# STM32.net
KiCad netlist of a schematic drawn in Altium Designer
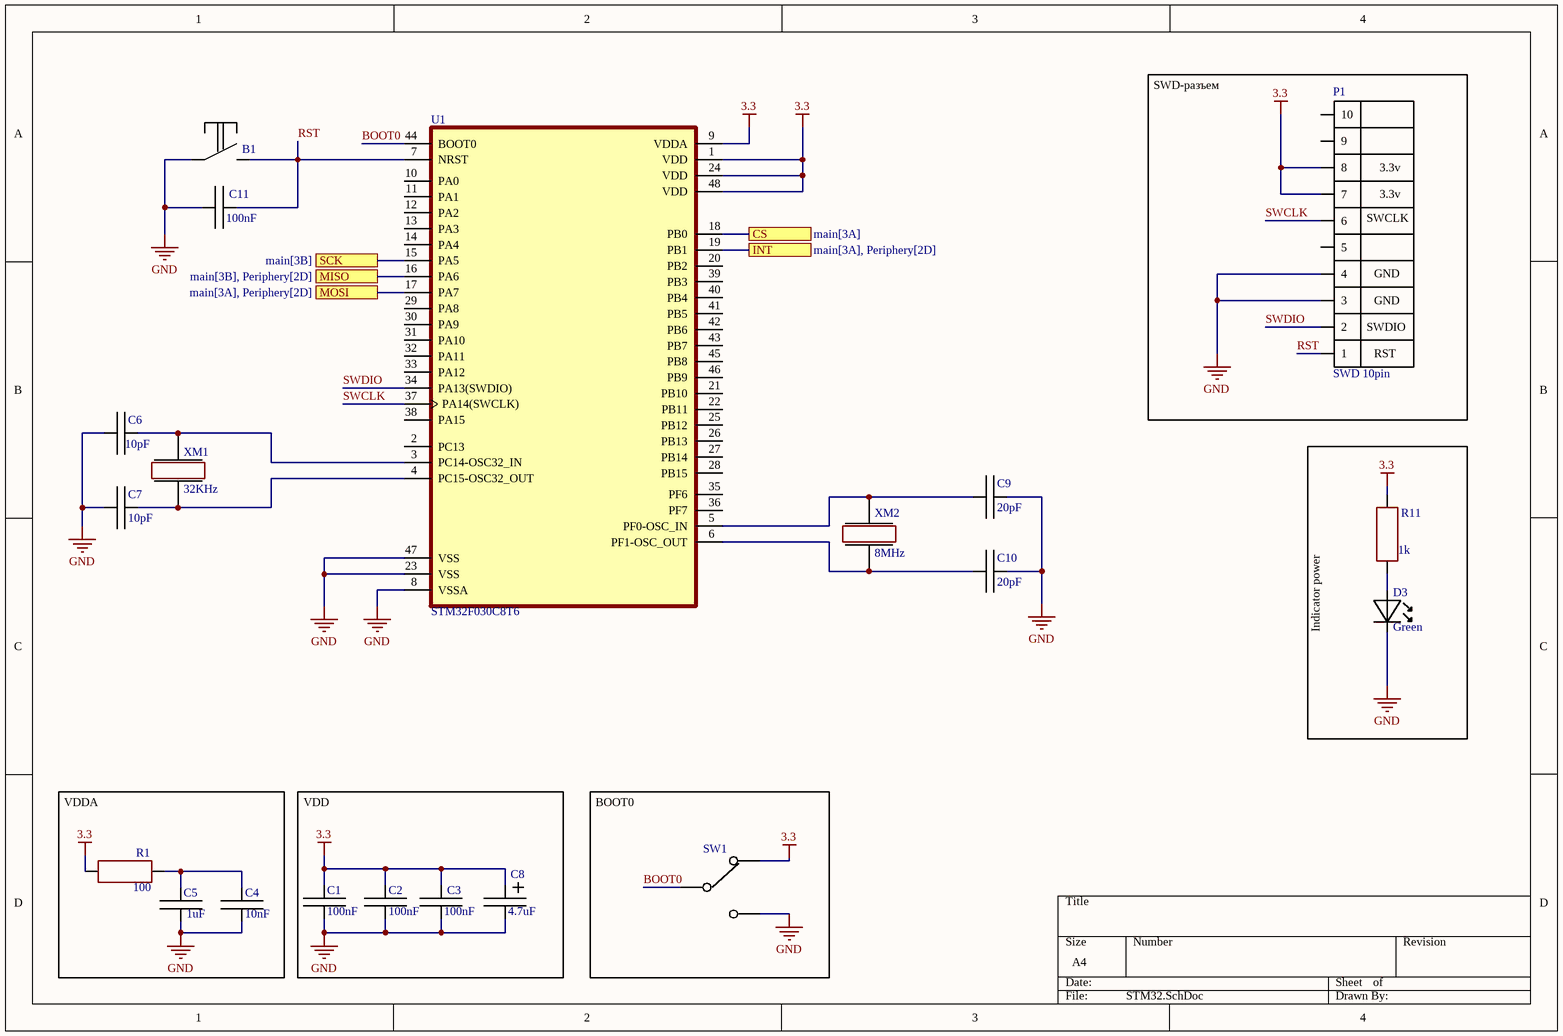
[diagram p0: STM32.SchDoc]

(export (version "E")
  (design (tool "Eeschema 10.0.6"))
  (components
    (comp (ref "B1")
      (value "Knopka")
      (footprint "knopka")
      (description "SMD")
      (libsource (lib "Integrated_Library1") (part "Knopka"))
    )
    (comp (ref "C1")
      (value "100nF")
      (footprint "C0805")
      (description "Керамический конденсатор. 1uF,10uF,106uF,33pF,100uF")
      (libsource (lib "Integrated_Library1") (part "C0805"))
    )
    (comp (ref "C2")
      (value "100nF")
      (footprint "C0805")
      (description "Керамический конденсатор. 1uF,10uF,106uF,33pF,100uF")
      (libsource (lib "Integrated_Library1") (part "C0805"))
    )
    (comp (ref "C3")
      (value "100nF")
      (footprint "C0805")
      (description "Керамический конденсатор. 1uF,10uF,106uF,33pF,100uF")
      (libsource (lib "Integrated_Library1") (part "C0805"))
    )
    (comp (ref "C4")
      (value "10nF")
      (footprint "C0805")
      (description "Керамический конденсатор. 1uF,10uF,106uF,33pF,100uF")
      (libsource (lib "Integrated_Library1") (part "C0805"))
    )
    (comp (ref "C5")
      (value "1uF")
      (footprint "C0805")
      (description "Керамический конденсатор. 1uF,10uF,106uF,33pF,100uF")
      (libsource (lib "Integrated_Library1") (part "C0805"))
    )
    (comp (ref "C6")
      (value "10pF")
      (footprint "C0805")
      (description "Керамический конденсатор. 1uF,10uF,106uF,33pF,100uF")
      (libsource (lib "Integrated_Library1") (part "C0805"))
    )
    (comp (ref "C7")
      (value "10pF")
      (footprint "C0805")
      (description "Керамический конденсатор. 1uF,10uF,106uF,33pF,100uF")
      (libsource (lib "Integrated_Library1") (part "C0805"))
    )
    (comp (ref "C8")
      (value "4.7uF")
      (footprint "CAP_3.5 (8x12мм)")
      (description "Электролит конденсатор (8x12мм)")
      (libsource (lib "Integrated_Library1") (part "C_3.5"))
    )
    (comp (ref "C9")
      (value "20pF")
      (footprint "C0805")
      (description "Керамический конденсатор. 1uF,10uF,106uF,33pF,100uF")
      (libsource (lib "Integrated_Library1") (part "C0805"))
    )
    (comp (ref "C10")
      (value "20pF")
      (footprint "C0805")
      (description "Керамический конденсатор. 1uF,10uF,106uF,33pF,100uF")
      (libsource (lib "Integrated_Library1") (part "C0805"))
    )
    (comp (ref "C11")
      (value "100nF")
      (footprint "C0805")
      (description "Керамический конденсатор. 1uF,10uF,106uF,33pF,100uF")
      (libsource (lib "Integrated_Library1") (part "C0805"))
    )
    (comp (ref "D3")
      (value "Green")
      (footprint "LED0805")
      (description "SMD 0805")
      (libsource (lib "Integrated_Library1") (part "Led"))
    )
    (comp (ref "P1")
      (value "SWD 10pin")
      (footprint "SWD 10 pin")
      (libsource (lib "Integrated_Library1") (part "SWD 10pin"))
    )
    (comp (ref "R1")
      (value "100")
      (footprint "R0805")
      (description "SMD")
      (libsource (lib "Integrated_Library1") (part "R0805"))
    )
    (comp (ref "R11")
      (value "1k")
      (footprint "R0805")
      (description "SMD")
      (libsource (lib "") (part "R0805_1"))
    )
    (comp (ref "SW1")
      (value "SW1")
      (footprint "PLS3")
      (description "для джампера")
      (libsource (lib "Integrated_Library1") (part "PLS3"))
    )
    (comp (ref "U1")
      (value "STM32F030C8T6")
      (footprint "STM32F030C8T6")
      (libsource (lib "Integrated_Library1") (part "STM32F030C8T6"))
    )
    (comp (ref "XM1")
      (value "32KHz")
      (footprint "Resonator")
      (libsource (lib "Integrated_Library1") (part "Resonator"))
    )
    (comp (ref "XM2")
      (value "8MHz")
      (footprint "Resonator")
      (libsource (lib "Integrated_Library1") (part "Resonator"))
    )
  )
  (nets
    (net (code "1") (name "/BOOT0") (class "Default")
      (node (ref "SW1") (pin "2") (pinfunction "5_2") (pintype "passive"))
      (node (ref "U1") (pin "44") (pinfunction "BOOT0_44") (pintype "passive"))
    )
    (net (code "2") (name "/CS") (class "Default")
      (node (ref "U1") (pin "18") (pinfunction "PB0_18") (pintype "passive"))
    )
    (net (code "3") (name "/INT") (class "Default")
      (node (ref "U1") (pin "19") (pinfunction "PB1_19") (pintype "passive"))
    )
    (net (code "4") (name "/MISO") (class "Default")
      (node (ref "U1") (pin "16") (pinfunction "PA6_16") (pintype "passive"))
    )
    (net (code "5") (name "/MOSI") (class "Default")
      (node (ref "U1") (pin "17") (pinfunction "PA7_17") (pintype "passive"))
    )
    (net (code "6") (name "/RST") (class "Default")
      (node (ref "B1") (pin "2") (pinfunction "2_2") (pintype "passive"))
      (node (ref "C11") (pin "2") (pinfunction "2_2") (pintype "passive"))
      (node (ref "P1") (pin "1") (pinfunction "1_1") (pintype "passive"))
      (node (ref "U1") (pin "7") (pinfunction "NRST_7") (pintype "passive"))
    )
    (net (code "7") (name "/SCK") (class "Default")
      (node (ref "U1") (pin "15") (pinfunction "PA5_15") (pintype "passive"))
    )
    (net (code "8") (name "/SWCLK") (class "Default")
      (node (ref "P1") (pin "6") (pinfunction "6_6") (pintype "passive"))
      (node (ref "U1") (pin "37") (pinfunction "PA14(SWCLK)_37") (pintype "passive"))
    )
    (net (code "9") (name "/SWDIO") (class "Default")
      (node (ref "P1") (pin "2") (pinfunction "2_2") (pintype "passive"))
      (node (ref "U1") (pin "34") (pinfunction "PA13(SWDIO)_34") (pintype "passive"))
    )
    (net (code "10") (name "3.3") (class "Default")
      (node (ref "C1") (pin "2") (pinfunction "2_2") (pintype "passive"))
      (node (ref "C2") (pin "2") (pinfunction "2_2") (pintype "passive"))
      (node (ref "C3") (pin "2") (pinfunction "2_2") (pintype "passive"))
      (node (ref "C8") (pin "1") (pinfunction "1_1") (pintype "passive"))
      (node (ref "P1") (pin "7") (pinfunction "7_7") (pintype "passive"))
      (node (ref "P1") (pin "8") (pinfunction "8_8") (pintype "passive"))
      (node (ref "R1") (pin "2") (pinfunction "2_2") (pintype "passive"))
      (node (ref "R11") (pin "2") (pinfunction "2_2") (pintype "passive"))
      (node (ref "SW1") (pin "1") (pinfunction "1_1") (pintype "passive"))
      (node (ref "U1") (pin "1") (pinfunction "VDD_1") (pintype "passive"))
      (node (ref "U1") (pin "24") (pinfunction "VDD_24") (pintype "passive"))
      (node (ref "U1") (pin "48") (pinfunction "VDD_48") (pintype "passive"))
      (node (ref "U1") (pin "9") (pinfunction "VDDA_9") (pintype "passive"))
    )
    (net (code "11") (name "GND") (class "Default")
      (node (ref "B1") (pin "1") (pinfunction "1_1") (pintype "passive"))
      (node (ref "C1") (pin "1") (pinfunction "1_1") (pintype "passive"))
      (node (ref "C10") (pin "2") (pinfunction "2_2") (pintype "passive"))
      (node (ref "C11") (pin "1") (pinfunction "1_1") (pintype "passive"))
      (node (ref "C2") (pin "1") (pinfunction "1_1") (pintype "passive"))
      (node (ref "C3") (pin "1") (pinfunction "1_1") (pintype "passive"))
      (node (ref "C4") (pin "1") (pinfunction "1_1") (pintype "passive"))
      (node (ref "C5") (pin "1") (pinfunction "1_1") (pintype "passive"))
      (node (ref "C6") (pin "1") (pinfunction "1_1") (pintype "passive"))
      (node (ref "C7") (pin "1") (pinfunction "1_1") (pintype "passive"))
      (node (ref "C8") (pin "2") (pinfunction "2_2") (pintype "passive"))
      (node (ref "C9") (pin "2") (pinfunction "2_2") (pintype "passive"))
      (node (ref "D3") (pin "C") (pinfunction "2_C") (pintype "passive"))
      (node (ref "P1") (pin "3") (pinfunction "3_3") (pintype "passive"))
      (node (ref "P1") (pin "4") (pinfunction "4_4") (pintype "passive"))
      (node (ref "SW1") (pin "3") (pinfunction "3_3") (pintype "passive"))
      (node (ref "U1") (pin "23") (pinfunction "VSS_23") (pintype "passive"))
      (node (ref "U1") (pin "47") (pinfunction "VSS_47") (pintype "passive"))
      (node (ref "U1") (pin "8") (pinfunction "VSSA_8") (pintype "passive"))
    )
    (net (code "12") (name "Net-(C4-Pad2)") (class "Default")
      (node (ref "C4") (pin "2") (pinfunction "2_2") (pintype "passive"))
      (node (ref "C5") (pin "2") (pinfunction "2_2") (pintype "passive"))
      (node (ref "R1") (pin "1") (pinfunction "1_1") (pintype "passive"))
    )
    (net (code "13") (name "Net-(D3-1)") (class "Default")
      (node (ref "D3") (pin "A") (pinfunction "1_A") (pintype "passive"))
      (node (ref "R11") (pin "1") (pinfunction "1_1") (pintype "passive"))
    )
    (net (code "14") (name "Net-(U1-PC14-OSC32_IN)") (class "Default")
      (node (ref "C6") (pin "2") (pinfunction "2_2") (pintype "passive"))
      (node (ref "U1") (pin "3") (pinfunction "PC14-OSC32_IN_3") (pintype "passive"))
      (node (ref "XM1") (pin "2") (pinfunction "2_2") (pintype "passive"))
    )
    (net (code "15") (name "Net-(U1-PC15-OSC32_OUT)") (class "Default")
      (node (ref "C7") (pin "2") (pinfunction "2_2") (pintype "passive"))
      (node (ref "U1") (pin "4") (pinfunction "PC15-OSC32_OUT_4") (pintype "passive"))
      (node (ref "XM1") (pin "1") (pinfunction "1_1") (pintype "passive"))
    )
    (net (code "16") (name "Net-(U1-PF0-OSC_IN)") (class "Default")
      (node (ref "C9") (pin "1") (pinfunction "1_1") (pintype "passive"))
      (node (ref "U1") (pin "5") (pinfunction "PF0-OSC_IN_5") (pintype "passive"))
      (node (ref "XM2") (pin "2") (pinfunction "2_2") (pintype "passive"))
    )
    (net (code "17") (name "Net-(U1-PF1-OSC_OUT)") (class "Default")
      (node (ref "C10") (pin "1") (pinfunction "1_1") (pintype "passive"))
      (node (ref "U1") (pin "6") (pinfunction "PF1-OSC_OUT_6") (pintype "passive"))
      (node (ref "XM2") (pin "1") (pinfunction "1_1") (pintype "passive"))
    )
    (net (code "18") (name "unconnected-(P1-Pad5)") (class "Default")
      (node (ref "P1") (pin "5") (pinfunction "5_5") (pintype "passive"))
    )
    (net (code "19") (name "unconnected-(P1-Pad9)") (class "Default")
      (node (ref "P1") (pin "9") (pinfunction "9_9") (pintype "passive"))
    )
    (net (code "20") (name "unconnected-(P1-Pad10)") (class "Default")
      (node (ref "P1") (pin "10") (pinfunction "10_10") (pintype "passive"))
    )
    (net (code "21") (name "unconnected-(U1-PA0-Pad10)") (class "Default")
      (node (ref "U1") (pin "10") (pinfunction "PA0_10") (pintype "passive"))
    )
    (net (code "22") (name "unconnected-(U1-PA1-Pad11)") (class "Default")
      (node (ref "U1") (pin "11") (pinfunction "PA1_11") (pintype "passive"))
    )
    (net (code "23") (name "unconnected-(U1-PA2-Pad12)") (class "Default")
      (node (ref "U1") (pin "12") (pinfunction "PA2_12") (pintype "passive"))
    )
    (net (code "24") (name "unconnected-(U1-PA3-Pad13)") (class "Default")
      (node (ref "U1") (pin "13") (pinfunction "PA3_13") (pintype "passive"))
    )
    (net (code "25") (name "unconnected-(U1-PA4-Pad14)") (class "Default")
      (node (ref "U1") (pin "14") (pinfunction "PA4_14") (pintype "passive"))
    )
    (net (code "26") (name "unconnected-(U1-PA8-Pad29)") (class "Default")
      (node (ref "U1") (pin "29") (pinfunction "PA8_29") (pintype "passive"))
    )
    (net (code "27") (name "unconnected-(U1-PA9-Pad30)") (class "Default")
      (node (ref "U1") (pin "30") (pinfunction "PA9_30") (pintype "passive"))
    )
    (net (code "28") (name "unconnected-(U1-PA10-Pad31)") (class "Default")
      (node (ref "U1") (pin "31") (pinfunction "PA10_31") (pintype "passive"))
    )
    (net (code "29") (name "unconnected-(U1-PA11-Pad32)") (class "Default")
      (node (ref "U1") (pin "32") (pinfunction "PA11_32") (pintype "passive"))
    )
    (net (code "30") (name "unconnected-(U1-PA12-Pad33)") (class "Default")
      (node (ref "U1") (pin "33") (pinfunction "PA12_33") (pintype "passive"))
    )
    (net (code "31") (name "unconnected-(U1-PA15-Pad38)") (class "Default")
      (node (ref "U1") (pin "38") (pinfunction "PA15_38") (pintype "passive"))
    )
    (net (code "32") (name "unconnected-(U1-PB2-Pad20)") (class "Default")
      (node (ref "U1") (pin "20") (pinfunction "PB2_20") (pintype "passive"))
    )
    (net (code "33") (name "unconnected-(U1-PB3-Pad39)") (class "Default")
      (node (ref "U1") (pin "39") (pinfunction "PB3_39") (pintype "passive"))
    )
    (net (code "34") (name "unconnected-(U1-PB4-Pad40)") (class "Default")
      (node (ref "U1") (pin "40") (pinfunction "PB4_40") (pintype "passive"))
    )
    (net (code "35") (name "unconnected-(U1-PB5-Pad41)") (class "Default")
      (node (ref "U1") (pin "41") (pinfunction "PB5_41") (pintype "passive"))
    )
    (net (code "36") (name "unconnected-(U1-PB6-Pad42)") (class "Default")
      (node (ref "U1") (pin "42") (pinfunction "PB6_42") (pintype "passive"))
    )
    (net (code "37") (name "unconnected-(U1-PB7-Pad43)") (class "Default")
      (node (ref "U1") (pin "43") (pinfunction "PB7_43") (pintype "passive"))
    )
    (net (code "38") (name "unconnected-(U1-PB8-Pad45)") (class "Default")
      (node (ref "U1") (pin "45") (pinfunction "PB8_45") (pintype "passive"))
    )
    (net (code "39") (name "unconnected-(U1-PB9-Pad46)") (class "Default")
      (node (ref "U1") (pin "46") (pinfunction "PB9_46") (pintype "passive"))
    )
    (net (code "40") (name "unconnected-(U1-PB10-Pad21)") (class "Default")
      (node (ref "U1") (pin "21") (pinfunction "PB10_21") (pintype "passive"))
    )
    (net (code "41") (name "unconnected-(U1-PB11-Pad22)") (class "Default")
      (node (ref "U1") (pin "22") (pinfunction "PB11_22") (pintype "passive"))
    )
    (net (code "42") (name "unconnected-(U1-PB12-Pad25)") (class "Default")
      (node (ref "U1") (pin "25") (pinfunction "PB12_25") (pintype "passive"))
    )
    (net (code "43") (name "unconnected-(U1-PB13-Pad26)") (class "Default")
      (node (ref "U1") (pin "26") (pinfunction "PB13_26") (pintype "passive"))
    )
    (net (code "44") (name "unconnected-(U1-PB14-Pad27)") (class "Default")
      (node (ref "U1") (pin "27") (pinfunction "PB14_27") (pintype "passive"))
    )
    (net (code "45") (name "unconnected-(U1-PB15-Pad28)") (class "Default")
      (node (ref "U1") (pin "28") (pinfunction "PB15_28") (pintype "passive"))
    )
    (net (code "46") (name "unconnected-(U1-PC13-Pad2)") (class "Default")
      (node (ref "U1") (pin "2") (pinfunction "PC13_2") (pintype "passive"))
    )
    (net (code "47") (name "unconnected-(U1-PF6-Pad35)") (class "Default")
      (node (ref "U1") (pin "35") (pinfunction "PF6_35") (pintype "passive"))
    )
    (net (code "48") (name "unconnected-(U1-PF7-Pad36)") (class "Default")
      (node (ref "U1") (pin "36") (pinfunction "PF7_36") (pintype "passive"))
    )
  )
)
